# MPU9250_and_TMP102.net
KiCad netlist of a schematic drawn in EAGLE
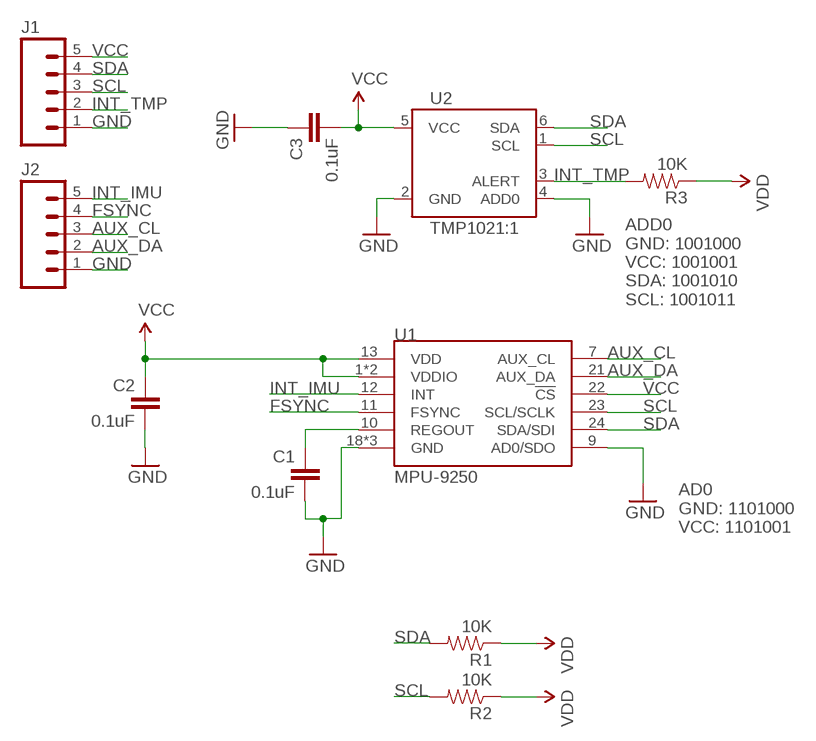
[diagram p0: schematic, sheet 1]

(export (version "E")
  (design (tool "Eeschema 10.0.6"))
  (components
    (comp (ref "C1")
      (value "0.1uF")
      (footprint "eagle-import:0603-CAP")
      (libsource (lib "eagle-import") (part "0.1UF-25V(+80/-20%)(0603)"))
    )
    (comp (ref "C2")
      (value "0.1uF")
      (footprint "eagle-import:0603-CAP")
      (libsource (lib "eagle-import") (part "0.1UF-25V(+80/-20%)(0603)"))
    )
    (comp (ref "C3")
      (value "0.1uF")
      (footprint "eagle-import:0603-CAP")
      (libsource (lib "eagle-import") (part "0.1UF-25V(+80/-20%)(0603)"))
    )
    (comp (ref "J1")
      (value "M05PTH")
      (footprint "eagle-import:1X05")
      (libsource (lib "eagle-import") (part "M05PTH"))
    )
    (comp (ref "J2")
      (value "M05PTH")
      (footprint "eagle-import:1X05")
      (libsource (lib "eagle-import") (part "M05PTH"))
    )
    (comp (ref "R1")
      (value "10K")
      (footprint "eagle-import:0603-RES")
      (libsource (lib "eagle-import") (part "10KOHM-1/10W-1%(0603)0603"))
    )
    (comp (ref "R2")
      (value "10K")
      (footprint "eagle-import:0603-RES")
      (libsource (lib "eagle-import") (part "10KOHM-1/10W-1%(0603)0603"))
    )
    (comp (ref "R3")
      (value "10K")
      (footprint "eagle-import:0603-RES")
      (libsource (lib "eagle-import") (part "10KOHM-1/10W-1%(0603)0603"))
    )
    (comp (ref "U1")
      (value "MPU-9250")
      (footprint "eagle-import:QFN24_PAD")
      (libsource (lib "eagle-import") (part "MPU-9250"))
    )
    (comp (ref "U2")
      (value "TMP1021:1")
      (footprint "eagle-import:SOT563-2")
      (libsource (lib "eagle-import") (part "TMP1021{colon}1"))
    )
  )
  (nets
    (net (code "1") (name "/AUX_CL") (class "Default")
      (node (ref "J2") (pin "3") (pinfunction "3_3") (pintype "passive"))
      (node (ref "U1") (pin "7") (pinfunction "AUX_CL_7") (pintype "bidirectional"))
    )
    (net (code "2") (name "/AUX_DA") (class "Default")
      (node (ref "J2") (pin "2") (pinfunction "2_2") (pintype "passive"))
      (node (ref "U1") (pin "21") (pinfunction "AUX_DA_21") (pintype "bidirectional"))
    )
    (net (code "3") (name "/FSYNC") (class "Default")
      (node (ref "J2") (pin "4") (pinfunction "4_4") (pintype "passive"))
      (node (ref "U1") (pin "11") (pinfunction "FSYNC_11") (pintype "bidirectional"))
    )
    (net (code "4") (name "/INT_IMU") (class "Default")
      (node (ref "J2") (pin "5") (pinfunction "5_5") (pintype "passive"))
      (node (ref "U1") (pin "12") (pinfunction "INT_12") (pintype "bidirectional"))
    )
    (net (code "5") (name "/INT_TMP") (class "Default")
      (node (ref "J1") (pin "2") (pinfunction "2_2") (pintype "passive"))
      (node (ref "R3") (pin "2") (pinfunction "2_2") (pintype "passive"))
      (node (ref "U2") (pin "3") (pinfunction "ALERT_3") (pintype "bidirectional"))
    )
    (net (code "6") (name "/SCL") (class "Default")
      (node (ref "J1") (pin "3") (pinfunction "3_3") (pintype "passive"))
      (node (ref "R2") (pin "2") (pinfunction "2_2") (pintype "passive"))
      (node (ref "U1") (pin "23") (pinfunction "SCL/SCLK_23") (pintype "bidirectional"))
      (node (ref "U2") (pin "1") (pinfunction "SCL_1") (pintype "bidirectional"))
    )
    (net (code "7") (name "/SDA") (class "Default")
      (node (ref "J1") (pin "4") (pinfunction "4_4") (pintype "passive"))
      (node (ref "R1") (pin "2") (pinfunction "2_2") (pintype "passive"))
      (node (ref "U1") (pin "24") (pinfunction "SDA/SDI_24") (pintype "bidirectional"))
      (node (ref "U2") (pin "6") (pinfunction "SDA_6") (pintype "bidirectional"))
    )
    (net (code "8") (name "GND") (class "Default")
      (node (ref "C1") (pin "2") (pinfunction "2_2") (pintype "passive"))
      (node (ref "C2") (pin "2") (pinfunction "2_2") (pintype "passive"))
      (node (ref "C3") (pin "1") (pinfunction "1_1") (pintype "passive"))
      (node (ref "J1") (pin "1") (pinfunction "1_1") (pintype "passive"))
      (node (ref "J2") (pin "1") (pinfunction "1_1") (pintype "passive"))
      (node (ref "U1") (pin "18") (pinfunction "GND_18") (pintype "bidirectional"))
      (node (ref "U1") (pin "20") (pinfunction "GND_20") (pintype "bidirectional"))
      (node (ref "U1") (pin "9") (pinfunction "AD0/SDO_9") (pintype "bidirectional"))
      (node (ref "U1") (pin "CENTER") (pinfunction "GND_CENTER") (pintype "bidirectional"))
      (node (ref "U2") (pin "2") (pinfunction "GND_2") (pintype "bidirectional"))
      (node (ref "U2") (pin "4") (pinfunction "ADD0_4") (pintype "bidirectional"))
    )
    (net (code "9") (name "Net-(U1-REGOUT)") (class "Default")
      (node (ref "C1") (pin "1") (pinfunction "1_1") (pintype "passive"))
      (node (ref "U1") (pin "10") (pinfunction "REGOUT_10") (pintype "bidirectional"))
    )
    (net (code "10") (name "VCC") (class "Default")
      (node (ref "C2") (pin "1") (pinfunction "1_1") (pintype "passive"))
      (node (ref "C3") (pin "2") (pinfunction "2_2") (pintype "passive"))
      (node (ref "J1") (pin "5") (pinfunction "5_5") (pintype "passive"))
      (node (ref "R1") (pin "1") (pinfunction "1_1") (pintype "passive"))
      (node (ref "R2") (pin "1") (pinfunction "1_1") (pintype "passive"))
      (node (ref "R3") (pin "1") (pinfunction "1_1") (pintype "passive"))
      (node (ref "U1") (pin "1") (pinfunction "VDDIO_1") (pintype "bidirectional"))
      (node (ref "U1") (pin "13") (pinfunction "VDD_13") (pintype "bidirectional"))
      (node (ref "U1") (pin "22") (pinfunction "~{CS}_22") (pintype "bidirectional"))
      (node (ref "U1") (pin "8") (pinfunction "VDDIO_8") (pintype "bidirectional"))
      (node (ref "U2") (pin "5") (pinfunction "VCC_5") (pintype "bidirectional"))
    )
  )
)
